# Battery_charger.net
KiCad netlist of a schematic drawn in Altium Designer
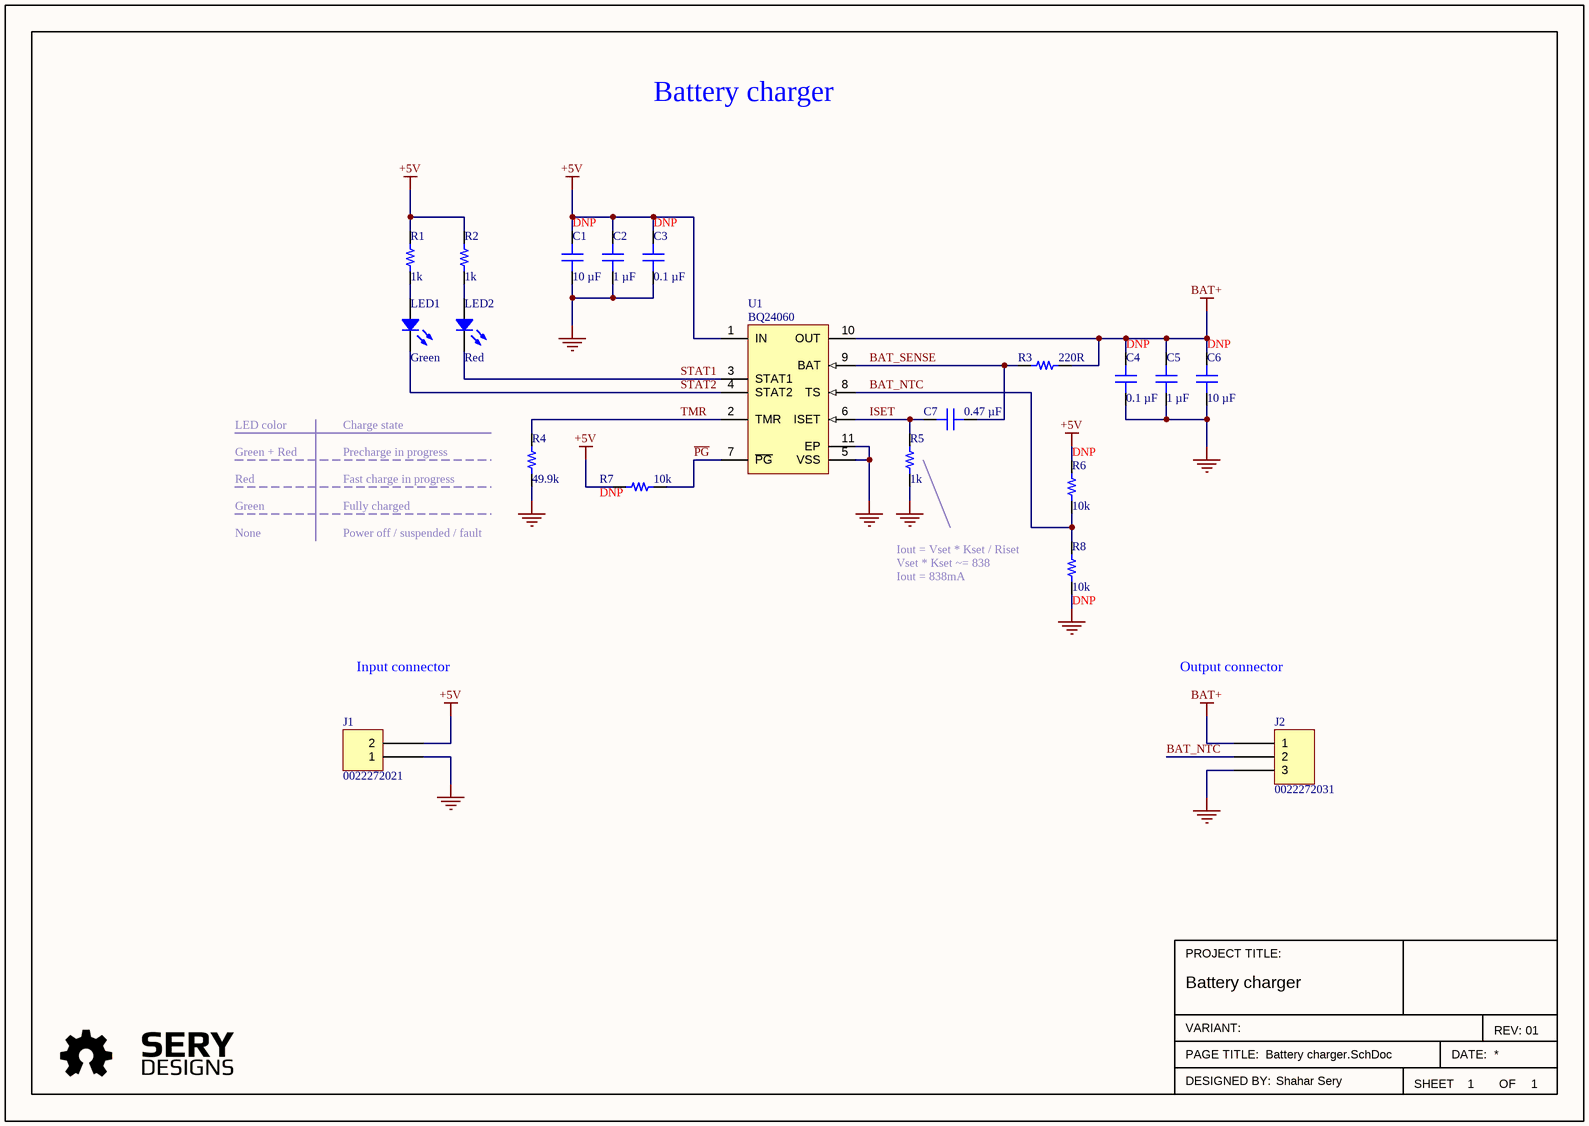
[diagram p0: Battery charger.SchDoc]

(export (version "E")
  (design (tool "Eeschema 10.0.6"))
  (components
    (comp (ref "C1")
      (value "10 µF")
      (footprint "CAP 0805_2012")
      (description "CAP CER 10UF 50V X5R 0805")
      (fields
        (field (name "PART NUMBER") "GRM21BR61H106ME43L")
        (field (name "MANUFACTURER") "Murata Electronics")
      )
      (libsource (lib "Celestial Altium Library - altium_library") (part "Capacitor"))
    )
    (comp (ref "C2")
      (value "1 µF")
      (footprint "CAP 0603_1608")
      (description "CAP CER 1UF 50V X7R 0603")
      (fields (field (name "PART NUMBER") "UMK107AB7105KA-T") (field (name "MANUFACTURER") "Taiyo Yuden"))
      (libsource (lib "Celestial Altium Library - altium_library") (part "Capacitor"))
    )
    (comp (ref "C3")
      (value "0.1 µF")
      (footprint "CAP 0402_1005")
      (description "CAP CER 0.1UF 50V X7R 0402")
      (fields
        (field (name "PART NUMBER") "CGA2B3X7R1H104M050BB")
        (field (name "MANUFACTURER") "TDK Corporation")
      )
      (libsource (lib "Celestial Altium Library - altium_library") (part "Capacitor"))
    )
    (comp (ref "C4")
      (value "0.1 µF")
      (footprint "CAP 0402_1005")
      (description "CAP CER 0.1UF 50V X7R 0402")
      (fields
        (field (name "PART NUMBER") "CGA2B3X7R1H104M050BB")
        (field (name "MANUFACTURER") "TDK Corporation")
      )
      (libsource (lib "Celestial Altium Library - altium_library") (part "Capacitor"))
    )
    (comp (ref "C5")
      (value "1 µF")
      (footprint "CAP 0603_1608")
      (description "CAP CER 1UF 50V X7R 0603")
      (fields (field (name "PART NUMBER") "UMK107AB7105KA-T") (field (name "MANUFACTURER") "Taiyo Yuden"))
      (libsource (lib "Celestial Altium Library - altium_library") (part "Capacitor"))
    )
    (comp (ref "C6")
      (value "10 µF")
      (footprint "CAP 0805_2012")
      (description "CAP CER 10UF 50V X5R 0805")
      (fields
        (field (name "PART NUMBER") "GRM21BR61H106ME43L")
        (field (name "MANUFACTURER") "Murata Electronics")
      )
      (libsource (lib "Celestial Altium Library - altium_library") (part "Capacitor"))
    )
    (comp (ref "C7")
      (value "0.47 µF")
      (footprint "CAP 0402_1005")
      (description "CAP CER 0.47UF 50V X5R 0402")
      (fields
        (field (name "PART NUMBER") "GRM155R61H474KE11D")
        (field (name "MANUFACTURER") "Murata Electronics")
      )
      (libsource (lib "Celestial Altium Library - altium_library") (part "Capacitor"))
    )
    (comp (ref "J1")
      (value "0022272021")
      (footprint "MOLEX KK 0022272021")
      (description "CONN HEADER VERT 2POS 2.54MM")
      (fields (field (name "MANUFACTURER") "Molex"))
      (libsource (lib "Celestial Altium Library - altium_library") (part "2 Pin"))
    )
    (comp (ref "J2")
      (value "0022272031")
      (footprint "MOLEX KK 0022272031")
      (description "CONN HEADER VERT 3POS 2.54MM")
      (fields (field (name "MANUFACTURER") "Molex"))
      (libsource (lib "Celestial Altium Library - altium_library") (part "3 Pin"))
    )
    (comp (ref "LED1")
      (value "Green")
      (footprint "LED 0603_1608 GREEN")
      (description "LED GREEN 0603 SMD")
      (fields (field (name "PART NUMBER") "5973316507F") (field (name "MANUFACTURER") "Dialight"))
      (libsource (lib "Celestial Altium Library - altium_library") (part "LED"))
    )
    (comp (ref "LED2")
      (value "Red")
      (footprint "LED 0603_1608 RED")
      (description "LED RED CLEAR 2SMD")
      (fields
        (field (name "PART NUMBER") "19-213/R6C-AP1Q2B/3T")
        (field (name "MANUFACTURER") "Everlight Electronics Co Ltd")
      )
      (libsource (lib "Celestial Altium Library - altium_library") (part "LED"))
    )
    (comp (ref "OSHW-logo1")
      (value "OSHW-logo")
      (footprint "Fabricated:OSHW-logo")
      (description "OSHW logo, no writing")
      (libsource (lib "Fabricated") (part "OSHW-logo"))
    )
    (comp (ref "R1")
      (value "1k")
      (footprint "RES 0402_1005")
      (description "RES SMD 1K OHM 1% 1/16W 0402")
      (fields (field (name "PART NUMBER") "SFR01MZPF1001") (field (name "MANUFACTURER") "Rohm Semiconductor"))
      (libsource (lib "Celestial Altium Library - altium_library") (part "Resistor"))
    )
    (comp (ref "R2")
      (value "1k")
      (footprint "RES 0402_1005")
      (description "RES SMD 1K OHM 1% 1/16W 0402")
      (fields (field (name "PART NUMBER") "SFR01MZPF1001") (field (name "MANUFACTURER") "Rohm Semiconductor"))
      (libsource (lib "Celestial Altium Library - altium_library") (part "Resistor"))
    )
    (comp (ref "R3")
      (value "220R")
      (footprint "RES 0402_1005")
      (description "RES SMD 220 OHM 1% 1/16W 0402")
      (fields (field (name "PART NUMBER") "RT0402FRE07220RL") (field (name "MANUFACTURER") "Yageo"))
      (libsource (lib "Celestial Altium Library - altium_library") (part "Resistor"))
    )
    (comp (ref "R4")
      (value "49.9k")
      (footprint "RES 0402_1005")
      (description "RES SMD 49.9K OHM 1% 1/16W 0402")
      (fields (field (name "PART NUMBER") "RT0402FRE0749K9L") (field (name "MANUFACTURER") "Yageo"))
      (libsource (lib "Celestial Altium Library - altium_library") (part "Resistor"))
    )
    (comp (ref "R5")
      (value "1k")
      (footprint "RES 0402_1005")
      (description "RES SMD 1K OHM 1% 1/16W 0402")
      (fields (field (name "PART NUMBER") "SFR01MZPF1001") (field (name "MANUFACTURER") "Rohm Semiconductor"))
      (libsource (lib "Celestial Altium Library - altium_library") (part "Resistor"))
    )
    (comp (ref "R6")
      (value "10k")
      (footprint "RES 0402_1005")
      (description "RES SMD 10K OHM 1% 1/16W 0402")
      (fields (field (name "PART NUMBER") "AC0402FR-0710KL") (field (name "MANUFACTURER") "Yageo"))
      (libsource (lib "Celestial Altium Library - altium_library") (part "Resistor"))
    )
    (comp (ref "R7")
      (value "10k")
      (footprint "RES 0402_1005")
      (description "RES SMD 10K OHM 1% 1/16W 0402")
      (fields (field (name "PART NUMBER") "AC0402FR-0710KL") (field (name "MANUFACTURER") "Yageo"))
      (libsource (lib "Celestial Altium Library - altium_library") (part "Resistor"))
    )
    (comp (ref "R8")
      (value "10k")
      (footprint "RES 0402_1005")
      (description "RES SMD 10K OHM 1% 1/16W 0402")
      (fields (field (name "PART NUMBER") "AC0402FR-0710KL") (field (name "MANUFACTURER") "Yageo"))
      (libsource (lib "Celestial Altium Library - altium_library") (part "Resistor"))
    )
    (comp (ref "SeryDesigns-logo1")
      (value "SeryDesigns-logo")
      (footprint "Fabricated:SeryDesigns-logo")
      (description "Sery designs logo")
      (libsource (lib "Fabricated") (part "SeryDesigns-logo"))
    )
    (comp (ref "U1")
      (value "BQ24060")
      (footprint "BQ24060-VSON")
      (description "IC, SMD, Battery Charger, Li-ion 1-Cell, 10VSON")
      (fields (field (name "MF") "Texas Instruments") (field (name "MPN") "BQ24060DRCT"))
      (libsource (lib "ICs") (part "BQ24060"))
    )
  )
  (nets
    (net (code "1") (name "+5V") (class "Default")
      (node (ref "C1") (pin "2") (pinfunction "2_2") (pintype "passive"))
      (node (ref "C2") (pin "2") (pinfunction "2_2") (pintype "passive"))
      (node (ref "C3") (pin "2") (pinfunction "2_2") (pintype "passive"))
      (node (ref "J1") (pin "2") (pinfunction "2_2") (pintype "passive"))
      (node (ref "R1") (pin "2") (pinfunction "2_2") (pintype "passive"))
      (node (ref "R2") (pin "2") (pinfunction "2_2") (pintype "passive"))
      (node (ref "R6") (pin "1") (pinfunction "1_1") (pintype "passive"))
      (node (ref "R7") (pin "2") (pinfunction "2_2") (pintype "passive"))
      (node (ref "U1") (pin "1") (pinfunction "IN_1") (pintype "power_in"))
    )
    (net (code "2") (name "/BAT_NTC") (class "Default")
      (node (ref "J2") (pin "2") (pinfunction "2_2") (pintype "passive"))
      (node (ref "R6") (pin "2") (pinfunction "2_2") (pintype "passive"))
      (node (ref "R8") (pin "1") (pinfunction "1_1") (pintype "passive"))
      (node (ref "U1") (pin "8") (pinfunction "TS_8") (pintype "input"))
    )
    (net (code "3") (name "/BAT_SENSE") (class "Default")
      (node (ref "C7") (pin "2") (pinfunction "2_2") (pintype "passive"))
      (node (ref "R3") (pin "1") (pinfunction "1_1") (pintype "passive"))
      (node (ref "U1") (pin "9") (pinfunction "BAT_9") (pintype "input"))
    )
    (net (code "4") (name "/ISET") (class "Default")
      (node (ref "C7") (pin "1") (pinfunction "1_1") (pintype "passive"))
      (node (ref "R5") (pin "2") (pinfunction "2_2") (pintype "passive"))
      (node (ref "U1") (pin "6") (pinfunction "ISET_6") (pintype "input"))
    )
    (net (code "5") (name "/STAT1") (class "Default")
      (node (ref "LED2") (pin "2") (pinfunction "2_2") (pintype "passive"))
      (node (ref "U1") (pin "3") (pinfunction "STAT1_3") (pintype "tri_state"))
    )
    (net (code "6") (name "/STAT2") (class "Default")
      (node (ref "LED1") (pin "2") (pinfunction "2_2") (pintype "passive"))
      (node (ref "U1") (pin "4") (pinfunction "STAT2_4") (pintype "tri_state"))
    )
    (net (code "7") (name "/TMR") (class "Default")
      (node (ref "R4") (pin "2") (pinfunction "2_2") (pintype "passive"))
      (node (ref "U1") (pin "2") (pinfunction "TMR_2") (pintype "passive"))
    )
    (net (code "8") (name "/~{PG}") (class "Default")
      (node (ref "R7") (pin "1") (pinfunction "1_1") (pintype "passive"))
      (node (ref "U1") (pin "7") (pinfunction "~{PG}_7") (pintype "tri_state"))
    )
    (net (code "9") (name "BAT+") (class "Default")
      (node (ref "C4") (pin "2") (pinfunction "2_2") (pintype "passive"))
      (node (ref "C5") (pin "2") (pinfunction "2_2") (pintype "passive"))
      (node (ref "C6") (pin "2") (pinfunction "2_2") (pintype "passive"))
      (node (ref "J2") (pin "1") (pinfunction "1_1") (pintype "passive"))
      (node (ref "R3") (pin "2") (pinfunction "2_2") (pintype "passive"))
      (node (ref "U1") (pin "10") (pinfunction "OUT_10") (pintype "power_in"))
    )
    (net (code "10") (name "GND") (class "Default")
      (node (ref "C1") (pin "1") (pinfunction "1_1") (pintype "passive"))
      (node (ref "C2") (pin "1") (pinfunction "1_1") (pintype "passive"))
      (node (ref "C3") (pin "1") (pinfunction "1_1") (pintype "passive"))
      (node (ref "C4") (pin "1") (pinfunction "1_1") (pintype "passive"))
      (node (ref "C5") (pin "1") (pinfunction "1_1") (pintype "passive"))
      (node (ref "C6") (pin "1") (pinfunction "1_1") (pintype "passive"))
      (node (ref "J1") (pin "1") (pinfunction "1_1") (pintype "passive"))
      (node (ref "J2") (pin "3") (pinfunction "3_3") (pintype "passive"))
      (node (ref "R4") (pin "1") (pinfunction "1_1") (pintype "passive"))
      (node (ref "R5") (pin "1") (pinfunction "1_1") (pintype "passive"))
      (node (ref "R8") (pin "2") (pinfunction "2_2") (pintype "passive"))
      (node (ref "U1") (pin "11") (pinfunction "EP_11") (pintype "power_in"))
      (node (ref "U1") (pin "5") (pinfunction "VSS_5") (pintype "power_in"))
    )
    (net (code "11") (name "Net-(LED1-Pad1)") (class "Default")
      (node (ref "LED1") (pin "1") (pinfunction "1_1") (pintype "passive"))
      (node (ref "R1") (pin "1") (pinfunction "1_1") (pintype "passive"))
    )
    (net (code "12") (name "Net-(LED2-Pad1)") (class "Default")
      (node (ref "LED2") (pin "1") (pinfunction "1_1") (pintype "passive"))
      (node (ref "R2") (pin "1") (pinfunction "1_1") (pintype "passive"))
    )
  )
)
